# PCB3.net
KiCad netlist of a schematic drawn in EAGLE
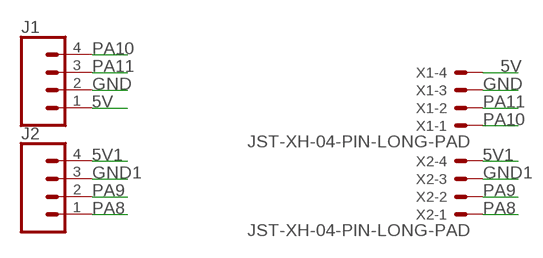
[diagram p0: schematic, sheet 1]

(export (version "E")
  (design (tool "Eeschema 10.0.6"))
  (components
    (comp (ref "J1")
      (value "CONN_04")
      (footprint "eagle-import:1X04")
      (libsource (lib "eagle-import") (part "CONN_04"))
    )
    (comp (ref "J2")
      (value "CONN_04")
      (footprint "eagle-import:1X04")
      (libsource (lib "eagle-import") (part "CONN_04"))
    )
    (comp (ref "X1")
      (value "JST-XH-04-PIN-LONG-PAD")
      (footprint "eagle-import:JST-XH-04-PACKAGE-LONG-PAD")
      (libsource (lib "eagle-import") (part "JST-XH-04-PIN-LONG-PAD"))
    )
    (comp (ref "X2")
      (value "JST-XH-04-PIN-LONG-PAD")
      (footprint "eagle-import:JST-XH-04-PACKAGE-LONG-PAD")
      (libsource (lib "eagle-import") (part "JST-XH-04-PIN-LONG-PAD"))
    )
  )
  (nets
    (net (code "1") (name "/5V") (class "Default")
      (node (ref "J1") (pin "1") (pinfunction "1_1") (pintype "passive"))
      (node (ref "X1") (pin "4") (pinfunction "S_4") (pintype "passive"))
    )
    (net (code "2") (name "/5V1") (class "Default")
      (node (ref "J2") (pin "4") (pinfunction "4_4") (pintype "passive"))
      (node (ref "X2") (pin "4") (pinfunction "S_4") (pintype "passive"))
    )
    (net (code "3") (name "/GND") (class "Default")
      (node (ref "J1") (pin "2") (pinfunction "2_2") (pintype "passive"))
      (node (ref "X1") (pin "3") (pinfunction "S_3") (pintype "passive"))
    )
    (net (code "4") (name "/GND1") (class "Default")
      (node (ref "J2") (pin "3") (pinfunction "3_3") (pintype "passive"))
      (node (ref "X2") (pin "3") (pinfunction "S_3") (pintype "passive"))
    )
    (net (code "5") (name "/PA8") (class "Default")
      (node (ref "J2") (pin "1") (pinfunction "1_1") (pintype "passive"))
      (node (ref "X2") (pin "1") (pinfunction "S_1") (pintype "passive"))
    )
    (net (code "6") (name "/PA9") (class "Default")
      (node (ref "J2") (pin "2") (pinfunction "2_2") (pintype "passive"))
      (node (ref "X2") (pin "2") (pinfunction "S_2") (pintype "passive"))
    )
    (net (code "7") (name "/PA10") (class "Default")
      (node (ref "J1") (pin "4") (pinfunction "4_4") (pintype "passive"))
      (node (ref "X1") (pin "1") (pinfunction "S_1") (pintype "passive"))
    )
    (net (code "8") (name "/PA11") (class "Default")
      (node (ref "J1") (pin "3") (pinfunction "3_3") (pintype "passive"))
      (node (ref "X1") (pin "2") (pinfunction "S_2") (pintype "passive"))
    )
  )
)
